# SCH_Mach_giao_tiep.net
KiCad netlist of a schematic drawn in Altium Designer
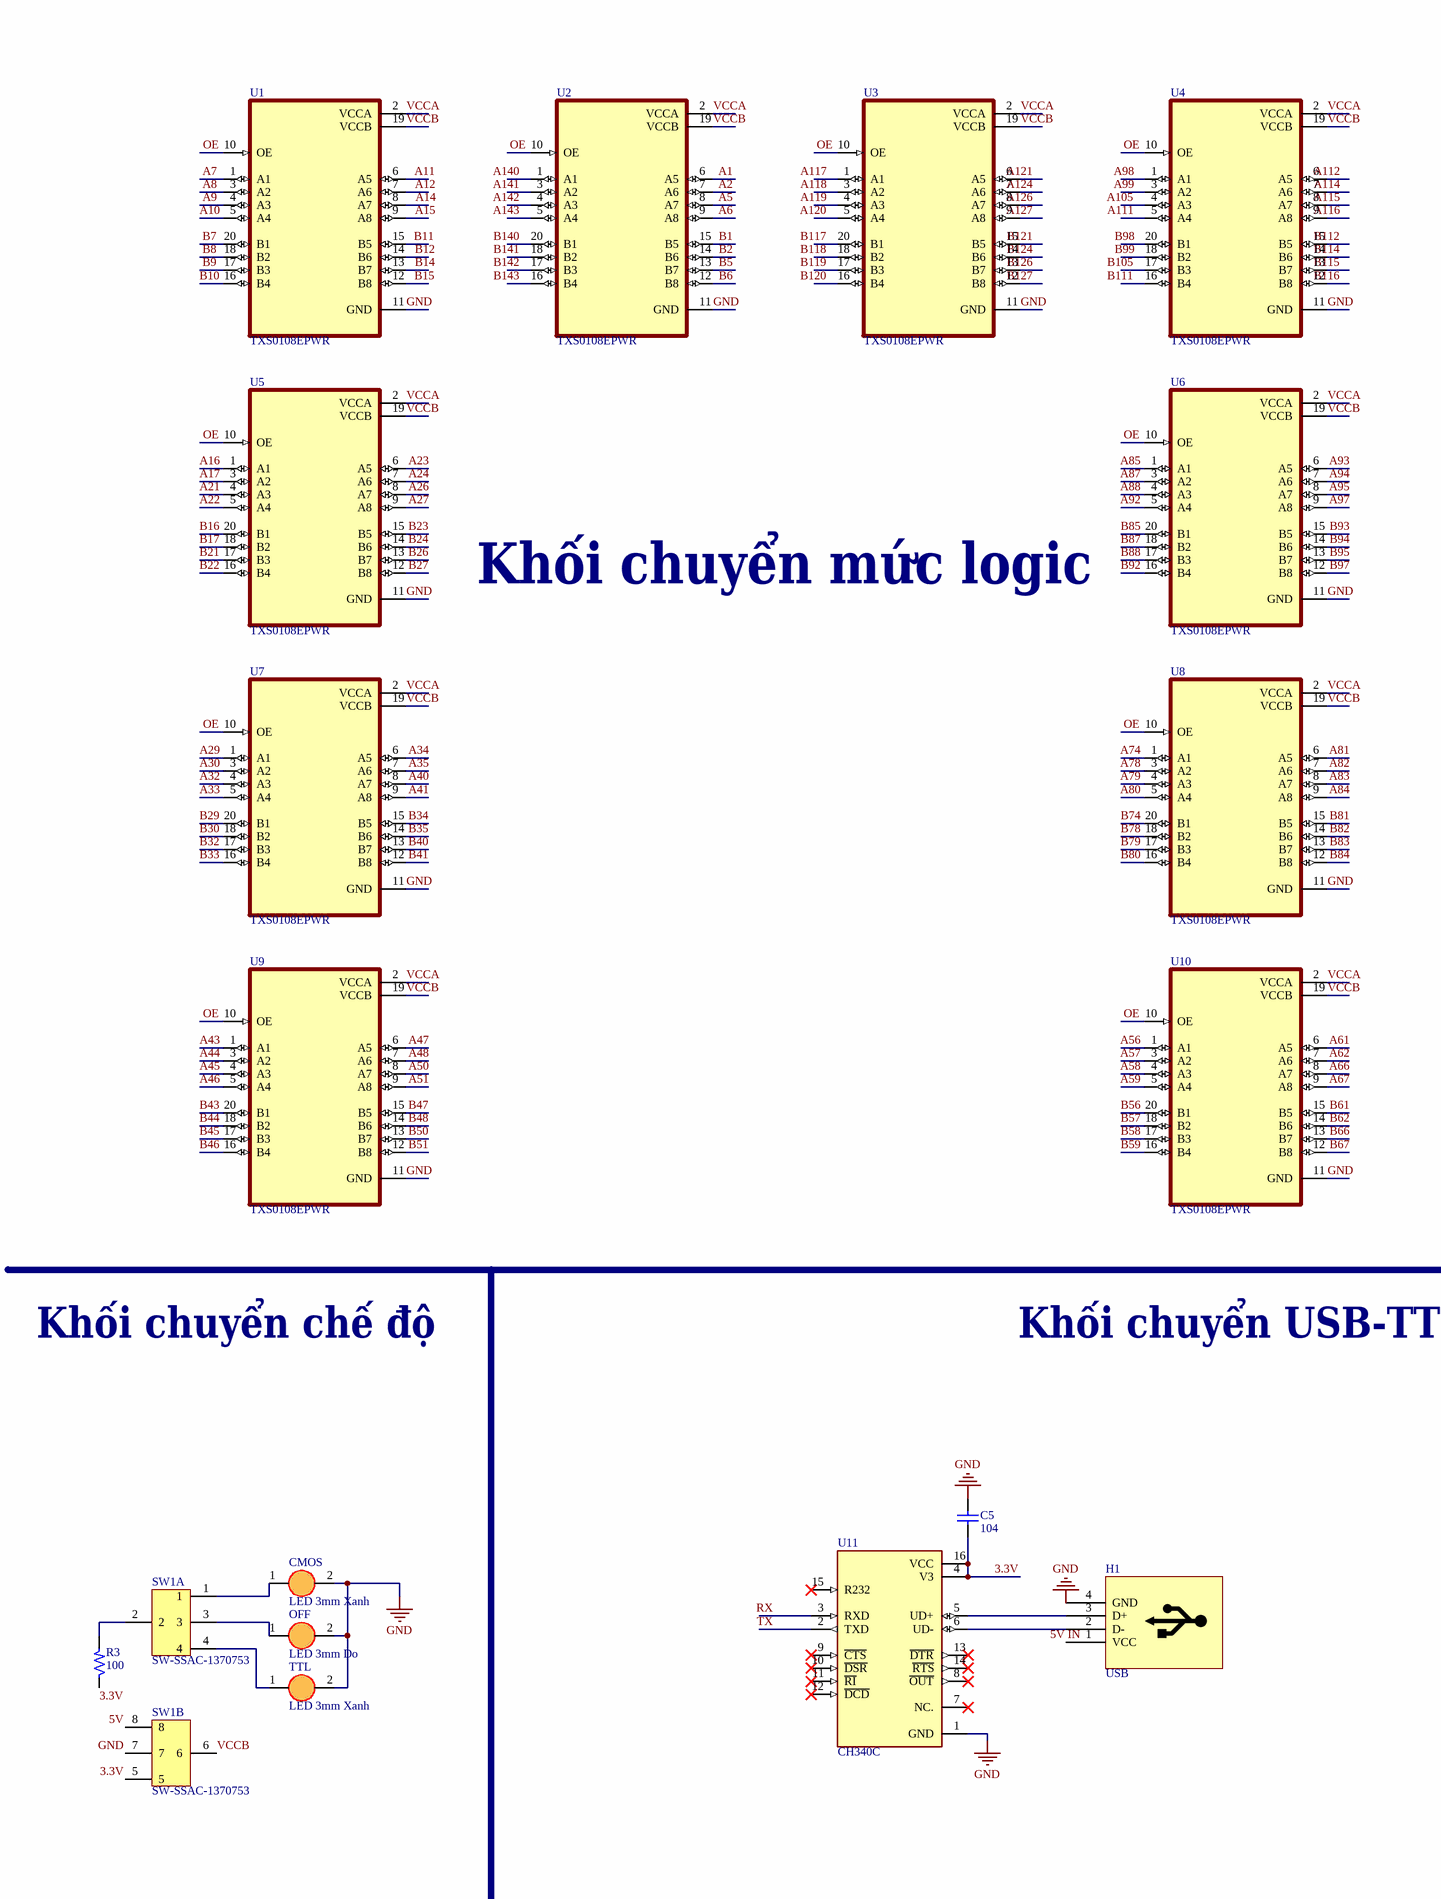
[diagram p0: SCH_Mach_giao_tiep.SchDoc, left]
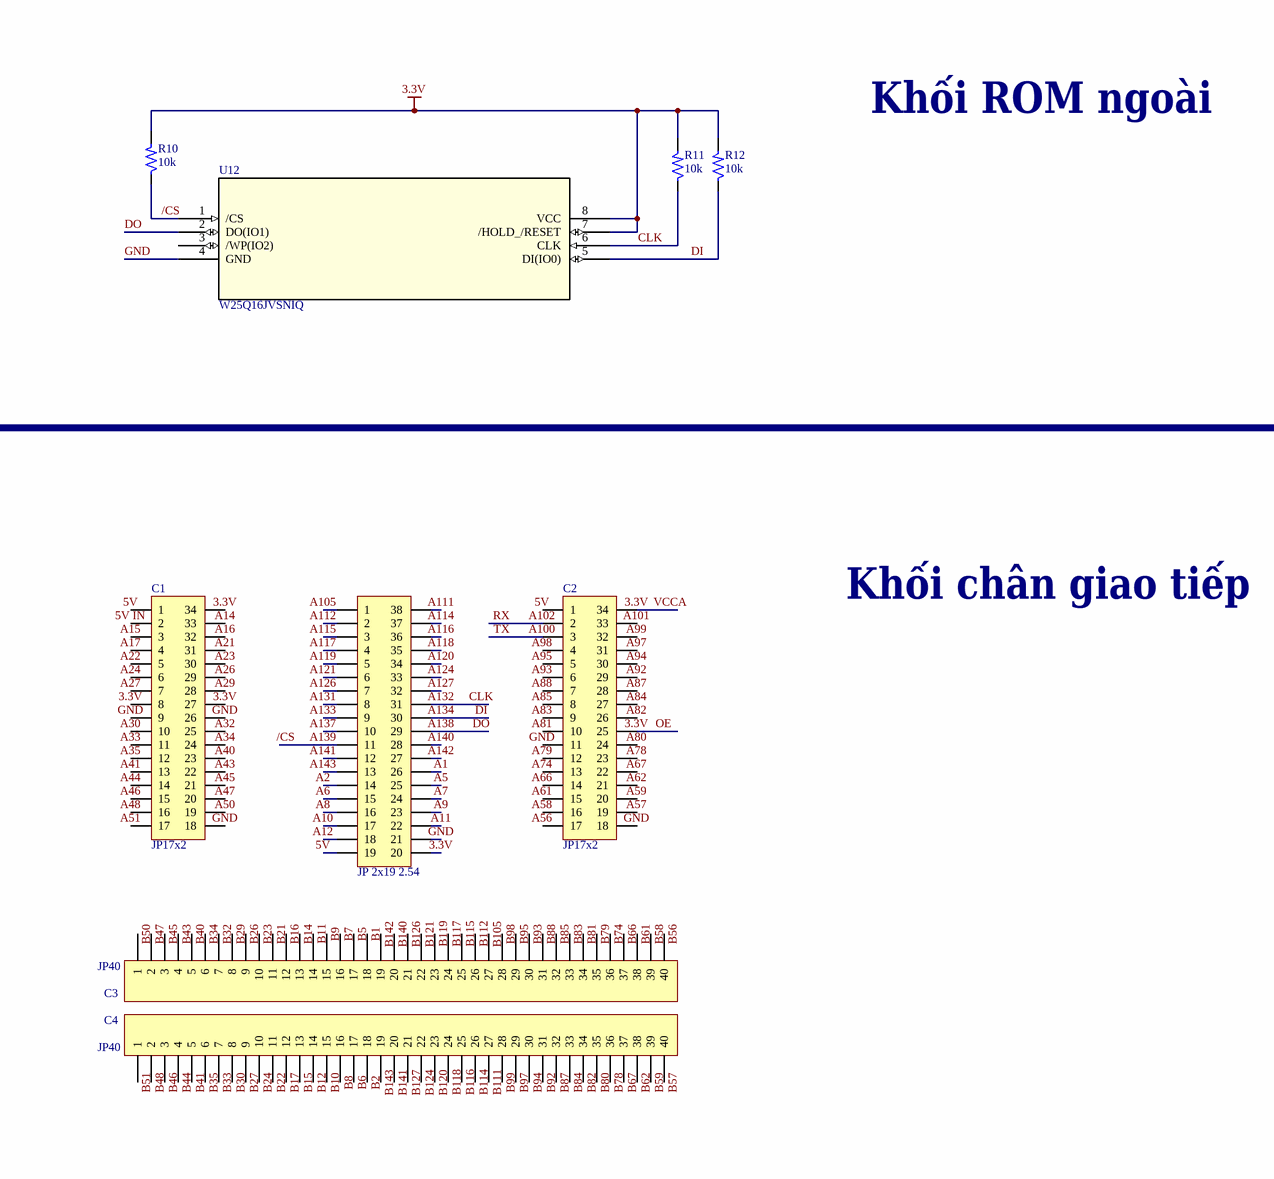
[diagram p1: SCH_Mach_giao_tiep.SchDoc, right]

(export (version "E")
  (design (tool "Eeschema 10.0.6"))
  (components
    (comp (ref "C1")
      (value "JP17x2")
      (footprint "JP17-C2T")
      (description "WR-PHD 2.54 mm Dual Socket Header")
      (fields
        (field (name "MANUFACTURER") "Würth Elektronik eiSos GmbH")
        (field (name "PARTNO") "61303421821")
        (field (name "CREATED BY") "Karrer Zheng")
      )
      (libsource (lib "LIBRARY") (part "JP17x2"))
    )
    (comp (ref "C2")
      (value "JP17x2")
      (footprint "JP17-C2T")
      (description "WR-PHD 2.54 mm Dual Socket Header")
      (fields
        (field (name "MANUFACTURER") "Würth Elektronik eiSos GmbH")
        (field (name "PARTNO") "61303421821")
        (field (name "CREATED BY") "Karrer Zheng")
      )
      (libsource (lib "LIBRARY") (part "JP17x2"))
    )
    (comp (ref "C3")
      (value "JP40")
      (footprint "JP40-D1T")
      (description "WR-PHD 2.54 mm Angled Socket Header")
      (fields
        (field (name "MANUFACTURER") "Würth Elektronik eiSos GmbH")
        (field (name "PARTNO") "613040143121")
        (field (name "CREATED BY") "Karrer Zheng")
      )
      (libsource (lib "") (part "JP40_1"))
    )
    (comp (ref "C4")
      (value "JP40")
      (footprint "JP40-D1T")
      (description "WR-PHD 2.54 mm Angled Socket Header")
      (fields
        (field (name "MANUFACTURER") "Würth Elektronik eiSos GmbH")
        (field (name "PARTNO") "613040143121")
        (field (name "CREATED BY") "Karrer Zheng")
      )
      (libsource (lib "LIBRARY") (part "JP40"))
    )
    (comp (ref "C5")
      (value "104")
      (footprint "tu gom")
      (description "Cắm")
      (libsource (lib "THU VIEN SCH") (part "Tu gom 104 50V"))
    )
    (comp (ref "CMOS")
      (value "LED 3mm Xanh")
      (footprint "LED 3MM XANH")
      (description "Cắm")
      (libsource (lib "THU VIEN SCH") (part "LED 3mm Xanh"))
    )
    (comp (ref "H1")
      (value "USB")
      (footprint "USB-B-STRANGE")
      (description "USB conector")
      (libsource (lib "Cty1") (part "USB"))
    )
    (comp (ref "JP1")
      (value "JP 2x19 2.54")
      (footprint "JP 2x20 CT")
      (description "Cắm")
      (libsource (lib "ThuVien") (part "JP 2x19 2.54 Cai Thang"))
    )
    (comp (ref "OFF")
      (value "LED 3mm Do")
      (footprint "LED 3mm Do")
      (description "Cắm")
      (libsource (lib "THU VIEN SCH") (part "LED 3mm Do"))
    )
    (comp (ref "R3")
      (value "100")
      (footprint "DIEN TRO 1/4 W")
      (description "Resistor 1/4W")
      (libsource (lib "Cty1") (part "Res"))
    )
    (comp (ref "R10")
      (value "10k")
      (footprint "SM-0805")
      (description "Resistor 1/4W")
      (libsource (lib "Cty1") (part "Res"))
    )
    (comp (ref "R11")
      (value "10k")
      (footprint "SM-0805")
      (description "Resistor 1/4W")
      (libsource (lib "Cty1") (part "Res"))
    )
    (comp (ref "R12")
      (value "10k")
      (footprint "SM-0805")
      (description "Resistor 1/4W")
      (libsource (lib "Cty1") (part "Res"))
    )
    (comp (ref "SW1")
      (value "SW-SSAC-1370753")
      (footprint "SW-SSAC-1370753")
      (libsource (lib "ThuVien") (part "SW-SSAC-1370753"))
    )
    (comp (ref "TTL")
      (value "LED 3mm Xanh")
      (footprint "LED 3MM XANH")
      (description "Cắm")
      (libsource (lib "THU VIEN SCH") (part "LED 3mm Xanh"))
    )
    (comp (ref "U1")
      (value "TXS0108EPWR")
      (footprint "SOP65P640X120-20N")
      (libsource (lib "ThuVien") (part "TXS0108EPWR"))
    )
    (comp (ref "U2")
      (value "TXS0108EPWR")
      (footprint "SOP65P640X120-20N")
      (libsource (lib "ThuVien") (part "TXS0108EPWR"))
    )
    (comp (ref "U3")
      (value "TXS0108EPWR")
      (footprint "SOP65P640X120-20N")
      (libsource (lib "ThuVien") (part "TXS0108EPWR"))
    )
    (comp (ref "U4")
      (value "TXS0108EPWR")
      (footprint "SOP65P640X120-20N")
      (libsource (lib "ThuVien") (part "TXS0108EPWR"))
    )
    (comp (ref "U5")
      (value "TXS0108EPWR")
      (footprint "SOP65P640X120-20N")
      (libsource (lib "ThuVien") (part "TXS0108EPWR"))
    )
    (comp (ref "U6")
      (value "TXS0108EPWR")
      (footprint "SOP65P640X120-20N")
      (libsource (lib "ThuVien") (part "TXS0108EPWR"))
    )
    (comp (ref "U7")
      (value "TXS0108EPWR")
      (footprint "SOP65P640X120-20N")
      (libsource (lib "ThuVien") (part "TXS0108EPWR"))
    )
    (comp (ref "U8")
      (value "TXS0108EPWR")
      (footprint "SOP65P640X120-20N")
      (libsource (lib "ThuVien") (part "TXS0108EPWR"))
    )
    (comp (ref "U9")
      (value "TXS0108EPWR")
      (footprint "SOP65P640X120-20N")
      (libsource (lib "ThuVien") (part "TXS0108EPWR"))
    )
    (comp (ref "U10")
      (value "TXS0108EPWR")
      (footprint "SOP65P640X120-20N")
      (libsource (lib "ThuVien") (part "TXS0108EPWR"))
    )
    (comp (ref "U11")
      (value "CH340C")
      (footprint "CH340C:SOIC127P600X180-16N")
      (description "USB to serial chip CH340")
      (fields (field (name "MF") "{'manufacturer': u'WCH'}"))
      (libsource (lib "ThuVien") (part "CH340C"))
    )
    (comp (ref "U12")
      (value "W25Q16JVSNIQ")
      (footprint "WIN_SS-8_WIN-M")
      (description "No Description Available")
      (fields (field (name "COPYRIGHT") "Copyright (C) 2022 Ultra Librarian. All rights reserved."))
      (libsource (lib "ThuVien") (part "W25Q16JVSNIQ"))
    )
  )
  (nets
    (net (code "1") (name "/5V") (class "Default")
      (node (ref "C1") (pin "1") (pinfunction "1_1") (pintype "passive"))
      (node (ref "C2") (pin "1") (pinfunction "1_1") (pintype "passive"))
      (node (ref "JP1") (pin "19") (pinfunction "19_19") (pintype "passive"))
      (node (ref "SW1") (pin "8") (pinfunction "8_8") (pintype "passive"))
    )
    (net (code "2") (name "/5V IN") (class "Default")
      (node (ref "C1") (pin "2") (pinfunction "2_2") (pintype "passive"))
      (node (ref "H1") (pin "1") (pinfunction "VCC_1") (pintype "passive"))
    )
    (net (code "3") (name "/A1") (class "Default")
      (node (ref "JP1") (pin "26") (pinfunction "26_26") (pintype "passive"))
      (node (ref "U2") (pin "6") (pinfunction "A5_6") (pintype "bidirectional"))
    )
    (net (code "4") (name "/A2") (class "Default")
      (node (ref "JP1") (pin "14") (pinfunction "14_14") (pintype "passive"))
      (node (ref "U2") (pin "7") (pinfunction "A6_7") (pintype "bidirectional"))
    )
    (net (code "5") (name "/A5") (class "Default")
      (node (ref "JP1") (pin "25") (pinfunction "25_25") (pintype "passive"))
      (node (ref "U2") (pin "8") (pinfunction "A7_8") (pintype "bidirectional"))
    )
    (net (code "6") (name "/A6") (class "Default")
      (node (ref "JP1") (pin "15") (pinfunction "15_15") (pintype "passive"))
      (node (ref "U2") (pin "9") (pinfunction "A8_9") (pintype "bidirectional"))
    )
    (net (code "7") (name "/A7") (class "Default")
      (node (ref "JP1") (pin "24") (pinfunction "24_24") (pintype "passive"))
      (node (ref "U1") (pin "1") (pinfunction "A1_1") (pintype "bidirectional"))
    )
    (net (code "8") (name "/A8") (class "Default")
      (node (ref "JP1") (pin "16") (pinfunction "16_16") (pintype "passive"))
      (node (ref "U1") (pin "3") (pinfunction "A2_3") (pintype "bidirectional"))
    )
    (net (code "9") (name "/A9") (class "Default")
      (node (ref "JP1") (pin "23") (pinfunction "23_23") (pintype "passive"))
      (node (ref "U1") (pin "4") (pinfunction "A3_4") (pintype "bidirectional"))
    )
    (net (code "10") (name "/A10") (class "Default")
      (node (ref "JP1") (pin "17") (pinfunction "17_17") (pintype "passive"))
      (node (ref "U1") (pin "5") (pinfunction "A4_5") (pintype "bidirectional"))
    )
    (net (code "11") (name "/A11") (class "Default")
      (node (ref "JP1") (pin "22") (pinfunction "22_22") (pintype "passive"))
      (node (ref "U1") (pin "6") (pinfunction "A5_6") (pintype "bidirectional"))
    )
    (net (code "12") (name "/A12") (class "Default")
      (node (ref "JP1") (pin "18") (pinfunction "18_18") (pintype "passive"))
      (node (ref "U1") (pin "7") (pinfunction "A6_7") (pintype "bidirectional"))
    )
    (net (code "13") (name "/A14") (class "Default")
      (node (ref "C1") (pin "33") (pinfunction "33_33") (pintype "passive"))
      (node (ref "U1") (pin "8") (pinfunction "A7_8") (pintype "bidirectional"))
    )
    (net (code "14") (name "/A15") (class "Default")
      (node (ref "C1") (pin "3") (pinfunction "3_3") (pintype "passive"))
      (node (ref "U1") (pin "9") (pinfunction "A8_9") (pintype "bidirectional"))
    )
    (net (code "15") (name "/A16") (class "Default")
      (node (ref "C1") (pin "32") (pinfunction "32_32") (pintype "passive"))
      (node (ref "U5") (pin "1") (pinfunction "A1_1") (pintype "bidirectional"))
    )
    (net (code "16") (name "/A17") (class "Default")
      (node (ref "C1") (pin "4") (pinfunction "4_4") (pintype "passive"))
      (node (ref "U5") (pin "3") (pinfunction "A2_3") (pintype "bidirectional"))
    )
    (net (code "17") (name "/A21") (class "Default")
      (node (ref "C1") (pin "31") (pinfunction "31_31") (pintype "passive"))
      (node (ref "U5") (pin "4") (pinfunction "A3_4") (pintype "bidirectional"))
    )
    (net (code "18") (name "/A22") (class "Default")
      (node (ref "C1") (pin "5") (pinfunction "5_5") (pintype "passive"))
      (node (ref "U5") (pin "5") (pinfunction "A4_5") (pintype "bidirectional"))
    )
    (net (code "19") (name "/A23") (class "Default")
      (node (ref "C1") (pin "30") (pinfunction "30_30") (pintype "passive"))
      (node (ref "U5") (pin "6") (pinfunction "A5_6") (pintype "bidirectional"))
    )
    (net (code "20") (name "/A24") (class "Default")
      (node (ref "C1") (pin "6") (pinfunction "6_6") (pintype "passive"))
      (node (ref "U5") (pin "7") (pinfunction "A6_7") (pintype "bidirectional"))
    )
    (net (code "21") (name "/A26") (class "Default")
      (node (ref "C1") (pin "29") (pinfunction "29_29") (pintype "passive"))
      (node (ref "U5") (pin "8") (pinfunction "A7_8") (pintype "bidirectional"))
    )
    (net (code "22") (name "/A27") (class "Default")
      (node (ref "C1") (pin "7") (pinfunction "7_7") (pintype "passive"))
      (node (ref "U5") (pin "9") (pinfunction "A8_9") (pintype "bidirectional"))
    )
    (net (code "23") (name "/A29") (class "Default")
      (node (ref "C1") (pin "28") (pinfunction "28_28") (pintype "passive"))
      (node (ref "U7") (pin "1") (pinfunction "A1_1") (pintype "bidirectional"))
    )
    (net (code "24") (name "/A30") (class "Default")
      (node (ref "C1") (pin "10") (pinfunction "10_10") (pintype "passive"))
      (node (ref "U7") (pin "3") (pinfunction "A2_3") (pintype "bidirectional"))
    )
    (net (code "25") (name "/A32") (class "Default")
      (node (ref "C1") (pin "25") (pinfunction "25_25") (pintype "passive"))
      (node (ref "U7") (pin "4") (pinfunction "A3_4") (pintype "bidirectional"))
    )
    (net (code "26") (name "/A33") (class "Default")
      (node (ref "C1") (pin "11") (pinfunction "11_11") (pintype "passive"))
      (node (ref "U7") (pin "5") (pinfunction "A4_5") (pintype "bidirectional"))
    )
    (net (code "27") (name "/A34") (class "Default")
      (node (ref "C1") (pin "24") (pinfunction "24_24") (pintype "passive"))
      (node (ref "U7") (pin "6") (pinfunction "A5_6") (pintype "bidirectional"))
    )
    (net (code "28") (name "/A35") (class "Default")
      (node (ref "C1") (pin "12") (pinfunction "12_12") (pintype "passive"))
      (node (ref "U7") (pin "7") (pinfunction "A6_7") (pintype "bidirectional"))
    )
    (net (code "29") (name "/A40") (class "Default")
      (node (ref "C1") (pin "23") (pinfunction "23_23") (pintype "passive"))
      (node (ref "U7") (pin "8") (pinfunction "A7_8") (pintype "bidirectional"))
    )
    (net (code "30") (name "/A41") (class "Default")
      (node (ref "C1") (pin "13") (pinfunction "13_13") (pintype "passive"))
      (node (ref "U7") (pin "9") (pinfunction "A8_9") (pintype "bidirectional"))
    )
    (net (code "31") (name "/A43") (class "Default")
      (node (ref "C1") (pin "22") (pinfunction "22_22") (pintype "passive"))
      (node (ref "U9") (pin "1") (pinfunction "A1_1") (pintype "bidirectional"))
    )
    (net (code "32") (name "/A44") (class "Default")
      (node (ref "C1") (pin "14") (pinfunction "14_14") (pintype "passive"))
      (node (ref "U9") (pin "3") (pinfunction "A2_3") (pintype "bidirectional"))
    )
    (net (code "33") (name "/A45") (class "Default")
      (node (ref "C1") (pin "21") (pinfunction "21_21") (pintype "passive"))
      (node (ref "U9") (pin "4") (pinfunction "A3_4") (pintype "bidirectional"))
    )
    (net (code "34") (name "/A46") (class "Default")
      (node (ref "C1") (pin "15") (pinfunction "15_15") (pintype "passive"))
      (node (ref "U9") (pin "5") (pinfunction "A4_5") (pintype "bidirectional"))
    )
    (net (code "35") (name "/A47") (class "Default")
      (node (ref "C1") (pin "20") (pinfunction "20_20") (pintype "passive"))
      (node (ref "U9") (pin "6") (pinfunction "A5_6") (pintype "bidirectional"))
    )
    (net (code "36") (name "/A48") (class "Default")
      (node (ref "C1") (pin "16") (pinfunction "16_16") (pintype "passive"))
      (node (ref "U9") (pin "7") (pinfunction "A6_7") (pintype "bidirectional"))
    )
    (net (code "37") (name "/A50") (class "Default")
      (node (ref "C1") (pin "19") (pinfunction "19_19") (pintype "passive"))
      (node (ref "U9") (pin "8") (pinfunction "A7_8") (pintype "bidirectional"))
    )
    (net (code "38") (name "/A51") (class "Default")
      (node (ref "C1") (pin "17") (pinfunction "17_17") (pintype "passive"))
      (node (ref "U9") (pin "9") (pinfunction "A8_9") (pintype "bidirectional"))
    )
    (net (code "39") (name "/A56") (class "Default")
      (node (ref "C2") (pin "17") (pinfunction "17_17") (pintype "passive"))
      (node (ref "U10") (pin "1") (pinfunction "A1_1") (pintype "bidirectional"))
    )
    (net (code "40") (name "/A57") (class "Default")
      (node (ref "C2") (pin "19") (pinfunction "19_19") (pintype "passive"))
      (node (ref "U10") (pin "3") (pinfunction "A2_3") (pintype "bidirectional"))
    )
    (net (code "41") (name "/A58") (class "Default")
      (node (ref "C2") (pin "16") (pinfunction "16_16") (pintype "passive"))
      (node (ref "U10") (pin "4") (pinfunction "A3_4") (pintype "bidirectional"))
    )
    (net (code "42") (name "/A59") (class "Default")
      (node (ref "C2") (pin "20") (pinfunction "20_20") (pintype "passive"))
      (node (ref "U10") (pin "5") (pinfunction "A4_5") (pintype "bidirectional"))
    )
    (net (code "43") (name "/A61") (class "Default")
      (node (ref "C2") (pin "15") (pinfunction "15_15") (pintype "passive"))
      (node (ref "U10") (pin "6") (pinfunction "A5_6") (pintype "bidirectional"))
    )
    (net (code "44") (name "/A62") (class "Default")
      (node (ref "C2") (pin "21") (pinfunction "21_21") (pintype "passive"))
      (node (ref "U10") (pin "7") (pinfunction "A6_7") (pintype "bidirectional"))
    )
    (net (code "45") (name "/A66") (class "Default")
      (node (ref "C2") (pin "14") (pinfunction "14_14") (pintype "passive"))
      (node (ref "U10") (pin "8") (pinfunction "A7_8") (pintype "bidirectional"))
    )
    (net (code "46") (name "/A67") (class "Default")
      (node (ref "C2") (pin "22") (pinfunction "22_22") (pintype "passive"))
      (node (ref "U10") (pin "9") (pinfunction "A8_9") (pintype "bidirectional"))
    )
    (net (code "47") (name "/A74") (class "Default")
      (node (ref "C2") (pin "13") (pinfunction "13_13") (pintype "passive"))
      (node (ref "U8") (pin "1") (pinfunction "A1_1") (pintype "bidirectional"))
    )
    (net (code "48") (name "/A78") (class "Default")
      (node (ref "C2") (pin "23") (pinfunction "23_23") (pintype "passive"))
      (node (ref "U8") (pin "3") (pinfunction "A2_3") (pintype "bidirectional"))
    )
    (net (code "49") (name "/A79") (class "Default")
      (node (ref "C2") (pin "12") (pinfunction "12_12") (pintype "passive"))
      (node (ref "U8") (pin "4") (pinfunction "A3_4") (pintype "bidirectional"))
    )
    (net (code "50") (name "/A80") (class "Default")
      (node (ref "C2") (pin "24") (pinfunction "24_24") (pintype "passive"))
      (node (ref "U8") (pin "5") (pinfunction "A4_5") (pintype "bidirectional"))
    )
    (net (code "51") (name "/A81") (class "Default")
      (node (ref "C2") (pin "10") (pinfunction "10_10") (pintype "passive"))
      (node (ref "U8") (pin "6") (pinfunction "A5_6") (pintype "bidirectional"))
    )
    (net (code "52") (name "/A82") (class "Default")
      (node (ref "C2") (pin "26") (pinfunction "26_26") (pintype "passive"))
      (node (ref "U8") (pin "7") (pinfunction "A6_7") (pintype "bidirectional"))
    )
    (net (code "53") (name "/A83") (class "Default")
      (node (ref "C2") (pin "9") (pinfunction "9_9") (pintype "passive"))
      (node (ref "U8") (pin "8") (pinfunction "A7_8") (pintype "bidirectional"))
    )
    (net (code "54") (name "/A84") (class "Default")
      (node (ref "C2") (pin "27") (pinfunction "27_27") (pintype "passive"))
      (node (ref "U8") (pin "9") (pinfunction "A8_9") (pintype "bidirectional"))
    )
    (net (code "55") (name "/A85") (class "Default")
      (node (ref "C2") (pin "8") (pinfunction "8_8") (pintype "passive"))
      (node (ref "U6") (pin "1") (pinfunction "A1_1") (pintype "bidirectional"))
    )
    (net (code "56") (name "/A87") (class "Default")
      (node (ref "C2") (pin "28") (pinfunction "28_28") (pintype "passive"))
      (node (ref "U6") (pin "3") (pinfunction "A2_3") (pintype "bidirectional"))
    )
    (net (code "57") (name "/A88") (class "Default")
      (node (ref "C2") (pin "7") (pinfunction "7_7") (pintype "passive"))
      (node (ref "U6") (pin "4") (pinfunction "A3_4") (pintype "bidirectional"))
    )
    (net (code "58") (name "/A92") (class "Default")
      (node (ref "C2") (pin "29") (pinfunction "29_29") (pintype "passive"))
      (node (ref "U6") (pin "5") (pinfunction "A4_5") (pintype "bidirectional"))
    )
    (net (code "59") (name "/A93") (class "Default")
      (node (ref "C2") (pin "6") (pinfunction "6_6") (pintype "passive"))
      (node (ref "U6") (pin "6") (pinfunction "A5_6") (pintype "bidirectional"))
    )
    (net (code "60") (name "/A94") (class "Default")
      (node (ref "C2") (pin "30") (pinfunction "30_30") (pintype "passive"))
      (node (ref "U6") (pin "7") (pinfunction "A6_7") (pintype "bidirectional"))
    )
    (net (code "61") (name "/A95") (class "Default")
      (node (ref "C2") (pin "5") (pinfunction "5_5") (pintype "passive"))
      (node (ref "U6") (pin "8") (pinfunction "A7_8") (pintype "bidirectional"))
    )
    (net (code "62") (name "/A97") (class "Default")
      (node (ref "C2") (pin "31") (pinfunction "31_31") (pintype "passive"))
      (node (ref "U6") (pin "9") (pinfunction "A8_9") (pintype "bidirectional"))
    )
    (net (code "63") (name "/A98") (class "Default")
      (node (ref "C2") (pin "4") (pinfunction "4_4") (pintype "passive"))
      (node (ref "U4") (pin "1") (pinfunction "A1_1") (pintype "bidirectional"))
    )
    (net (code "64") (name "/A99") (class "Default")
      (node (ref "C2") (pin "32") (pinfunction "32_32") (pintype "passive"))
      (node (ref "U4") (pin "3") (pinfunction "A2_3") (pintype "bidirectional"))
    )
    (net (code "65") (name "/A100") (class "Default")
      (node (ref "C2") (pin "3") (pinfunction "3_3") (pintype "passive"))
      (node (ref "U11") (pin "2") (pinfunction "TXD_2") (pintype "output"))
    )
    (net (code "66") (name "/A101") (class "Default")
      (node (ref "C2") (pin "33") (pinfunction "33_33") (pintype "passive"))
    )
    (net (code "67") (name "/A102") (class "Default")
      (node (ref "C2") (pin "2") (pinfunction "2_2") (pintype "passive"))
      (node (ref "U11") (pin "3") (pinfunction "RXD_3") (pintype "input"))
    )
    (net (code "68") (name "/A105") (class "Default")
      (node (ref "JP1") (pin "1") (pinfunction "1_1") (pintype "passive"))
      (node (ref "U4") (pin "4") (pinfunction "A3_4") (pintype "bidirectional"))
    )
    (net (code "69") (name "/A111") (class "Default")
      (node (ref "JP1") (pin "38") (pinfunction "38_38") (pintype "passive"))
      (node (ref "U4") (pin "5") (pinfunction "A4_5") (pintype "bidirectional"))
    )
    (net (code "70") (name "/A112") (class "Default")
      (node (ref "JP1") (pin "2") (pinfunction "2_2") (pintype "passive"))
      (node (ref "U4") (pin "6") (pinfunction "A5_6") (pintype "bidirectional"))
    )
    (net (code "71") (name "/A114") (class "Default")
      (node (ref "JP1") (pin "37") (pinfunction "37_37") (pintype "passive"))
      (node (ref "U4") (pin "7") (pinfunction "A6_7") (pintype "bidirectional"))
    )
    (net (code "72") (name "/A115") (class "Default")
      (node (ref "JP1") (pin "3") (pinfunction "3_3") (pintype "passive"))
      (node (ref "U4") (pin "8") (pinfunction "A7_8") (pintype "bidirectional"))
    )
    (net (code "73") (name "/A116") (class "Default")
      (node (ref "JP1") (pin "36") (pinfunction "36_36") (pintype "passive"))
      (node (ref "U4") (pin "9") (pinfunction "A8_9") (pintype "bidirectional"))
    )
    (net (code "74") (name "/A117") (class "Default")
      (node (ref "JP1") (pin "4") (pinfunction "4_4") (pintype "passive"))
      (node (ref "U3") (pin "1") (pinfunction "A1_1") (pintype "bidirectional"))
    )
    (net (code "75") (name "/A118") (class "Default")
      (node (ref "JP1") (pin "35") (pinfunction "35_35") (pintype "passive"))
      (node (ref "U3") (pin "3") (pinfunction "A2_3") (pintype "bidirectional"))
    )
    (net (code "76") (name "/A119") (class "Default")
      (node (ref "JP1") (pin "5") (pinfunction "5_5") (pintype "passive"))
      (node (ref "U3") (pin "4") (pinfunction "A3_4") (pintype "bidirectional"))
    )
    (net (code "77") (name "/A120") (class "Default")
      (node (ref "JP1") (pin "34") (pinfunction "34_34") (pintype "passive"))
      (node (ref "U3") (pin "5") (pinfunction "A4_5") (pintype "bidirectional"))
    )
    (net (code "78") (name "/A121") (class "Default")
      (node (ref "JP1") (pin "6") (pinfunction "6_6") (pintype "passive"))
      (node (ref "U3") (pin "6") (pinfunction "A5_6") (pintype "bidirectional"))
    )
    (net (code "79") (name "/A124") (class "Default")
      (node (ref "JP1") (pin "33") (pinfunction "33_33") (pintype "passive"))
      (node (ref "U3") (pin "7") (pinfunction "A6_7") (pintype "bidirectional"))
    )
    (net (code "80") (name "/A126") (class "Default")
      (node (ref "JP1") (pin "7") (pinfunction "7_7") (pintype "passive"))
      (node (ref "U3") (pin "8") (pinfunction "A7_8") (pintype "bidirectional"))
    )
    (net (code "81") (name "/A127") (class "Default")
      (node (ref "JP1") (pin "32") (pinfunction "32_32") (pintype "passive"))
      (node (ref "U3") (pin "9") (pinfunction "A8_9") (pintype "bidirectional"))
    )
    (net (code "82") (name "/A131") (class "Default")
      (node (ref "JP1") (pin "8") (pinfunction "8_8") (pintype "passive"))
    )
    (net (code "83") (name "/A132") (class "Default")
      (node (ref "JP1") (pin "31") (pinfunction "31_31") (pintype "passive"))
      (node (ref "R11") (pin "1") (pinfunction "1_1") (pintype "passive"))
      (node (ref "U12") (pin "6") (pinfunction "CLK_6") (pintype "input"))
    )
    (net (code "84") (name "/A133") (class "Default")
      (node (ref "JP1") (pin "9") (pinfunction "9_9") (pintype "passive"))
    )
    (net (code "85") (name "/A134") (class "Default")
      (node (ref "JP1") (pin "30") (pinfunction "30_30") (pintype "passive"))
      (node (ref "R12") (pin "1") (pinfunction "1_1") (pintype "passive"))
      (node (ref "U12") (pin "5") (pinfunction "DI(IO0)_5") (pintype "bidirectional"))
    )
    (net (code "86") (name "/A137") (class "Default")
      (node (ref "JP1") (pin "10") (pinfunction "10_10") (pintype "passive"))
    )
    (net (code "87") (name "/A138") (class "Default")
      (node (ref "JP1") (pin "29") (pinfunction "29_29") (pintype "passive"))
      (node (ref "U12") (pin "2") (pinfunction "DO(IO1)_2") (pintype "bidirectional"))
    )
    (net (code "88") (name "/A139") (class "Default")
      (node (ref "JP1") (pin "11") (pinfunction "11_11") (pintype "passive"))
      (node (ref "R10") (pin "1") (pinfunction "1_1") (pintype "passive"))
      (node (ref "U12") (pin "1") (pinfunction "/CS_1") (pintype "input"))
    )
    (net (code "89") (name "/A140") (class "Default")
      (node (ref "JP1") (pin "28") (pinfunction "28_28") (pintype "passive"))
      (node (ref "U2") (pin "1") (pinfunction "A1_1") (pintype "bidirectional"))
    )
    (net (code "90") (name "/A141") (class "Default")
      (node (ref "JP1") (pin "12") (pinfunction "12_12") (pintype "passive"))
      (node (ref "U2") (pin "3") (pinfunction "A2_3") (pintype "bidirectional"))
    )
    (net (code "91") (name "/A142") (class "Default")
      (node (ref "JP1") (pin "27") (pinfunction "27_27") (pintype "passive"))
      (node (ref "U2") (pin "4") (pinfunction "A3_4") (pintype "bidirectional"))
    )
    (net (code "92") (name "/A143") (class "Default")
      (node (ref "JP1") (pin "13") (pinfunction "13_13") (pintype "passive"))
      (node (ref "U2") (pin "5") (pinfunction "A4_5") (pintype "bidirectional"))
    )
    (net (code "93") (name "/B1") (class "Default")
      (node (ref "C3") (pin "18") (pinfunction "18_18") (pintype "passive"))
      (node (ref "U2") (pin "15") (pinfunction "B5_15") (pintype "bidirectional"))
    )
    (net (code "94") (name "/B2") (class "Default")
      (node (ref "C4") (pin "18") (pinfunction "18_18") (pintype "passive"))
      (node (ref "U2") (pin "14") (pinfunction "B6_14") (pintype "bidirectional"))
    )
    (net (code "95") (name "/B5") (class "Default")
      (node (ref "C3") (pin "17") (pinfunction "17_17") (pintype "passive"))
      (node (ref "U2") (pin "13") (pinfunction "B7_13") (pintype "bidirectional"))
    )
    (net (code "96") (name "/B6") (class "Default")
      (node (ref "C4") (pin "17") (pinfunction "17_17") (pintype "passive"))
      (node (ref "U2") (pin "12") (pinfunction "B8_12") (pintype "bidirectional"))
    )
    (net (code "97") (name "/B7") (class "Default")
      (node (ref "C3") (pin "16") (pinfunction "16_16") (pintype "passive"))
      (node (ref "U1") (pin "20") (pinfunction "B1_20") (pintype "bidirectional"))
    )
    (net (code "98") (name "/B8") (class "Default")
      (node (ref "C4") (pin "16") (pinfunction "16_16") (pintype "passive"))
      (node (ref "U1") (pin "18") (pinfunction "B2_18") (pintype "bidirectional"))
    )
    (net (code "99") (name "/B9") (class "Default")
      (node (ref "C3") (pin "15") (pinfunction "15_15") (pintype "passive"))
      (node (ref "U1") (pin "17") (pinfunction "B3_17") (pintype "bidirectional"))
    )
    (net (code "100") (name "/B10") (class "Default")
      (node (ref "C4") (pin "15") (pinfunction "15_15") (pintype "passive"))
      (node (ref "U1") (pin "16") (pinfunction "B4_16") (pintype "bidirectional"))
    )
    (net (code "101") (name "/B11") (class "Default")
      (node (ref "C3") (pin "14") (pinfunction "14_14") (pintype "passive"))
      (node (ref "U1") (pin "15") (pinfunction "B5_15") (pintype "bidirectional"))
    )
    (net (code "102") (name "/B12") (class "Default")
      (node (ref "C4") (pin "14") (pinfunction "14_14") (pintype "passive"))
      (node (ref "U1") (pin "14") (pinfunction "B6_14") (pintype "bidirectional"))
    )
    (net (code "103") (name "/B14") (class "Default")
      (node (ref "C3") (pin "13") (pinfunction "13_13") (pintype "passive"))
      (node (ref "U1") (pin "13") (pinfunction "B7_13") (pintype "bidirectional"))
    )
    (net (code "104") (name "/B15") (class "Default")
      (node (ref "C4") (pin "13") (pinfunction "13_13") (pintype "passive"))
      (node (ref "U1") (pin "12") (pinfunction "B8_12") (pintype "bidirectional"))
    )
    (net (code "105") (name "/B16") (class "Default")
      (node (ref "C3") (pin "12") (pinfunction "12_12") (pintype "passive"))
      (node (ref "U5") (pin "20") (pinfunction "B1_20") (pintype "bidirectional"))
    )
    (net (code "106") (name "/B17") (class "Default")
      (node (ref "C4") (pin "12") (pinfunction "12_12") (pintype "passive"))
      (node (ref "U5") (pin "18") (pinfunction "B2_18") (pintype "bidirectional"))
    )
    (net (code "107") (name "/B21") (class "Default")
      (node (ref "C3") (pin "11") (pinfunction "11_11") (pintype "passive"))
      (node (ref "U5") (pin "17") (pinfunction "B3_17") (pintype "bidirectional"))
    )
    (net (code "108") (name "/B22") (class "Default")
      (node (ref "C4") (pin "11") (pinfunction "11_11") (pintype "passive"))
      (node (ref "U5") (pin "16") (pinfunction "B4_16") (pintype "bidirectional"))
    )
    (net (code "109") (name "/B23") (class "Default")
      (node (ref "C3") (pin "10") (pinfunction "10_10") (pintype "passive"))
      (node (ref "U5") (pin "15") (pinfunction "B5_15") (pintype "bidirectional"))
    )
    (net (code "110") (name "/B24") (class "Default")
      (node (ref "C4") (pin "10") (pinfunction "10_10") (pintype "passive"))
      (node (ref "U5") (pin "14") (pinfunction "B6_14") (pintype "bidirectional"))
    )
    (net (code "111") (name "/B26") (class "Default")
      (node (ref "C3") (pin "9") (pinfunction "9_9") (pintype "passive"))
      (node (ref "U5") (pin "13") (pinfunction "B7_13") (pintype "bidirectional"))
    )
    (net (code "112") (name "/B27") (class "Default")
      (node (ref "C4") (pin "9") (pinfunction "9_9") (pintype "passive"))
      (node (ref "U5") (pin "12") (pinfunction "B8_12") (pintype "bidirectional"))
    )
    (net (code "113") (name "/B29") (class "Default")
      (node (ref "C3") (pin "8") (pinfunction "8_8") (pintype "passive"))
      (node (ref "U7") (pin "20") (pinfunction "B1_20") (pintype "bidirectional"))
    )
    (net (code "114") (name "/B30") (class "Default")
      (node (ref "C4") (pin "8") (pinfunction "8_8") (pintype "passive"))
      (node (ref "U7") (pin "18") (pinfunction "B2_18") (pintype "bidirectional"))
    )
    (net (code "115") (name "/B32") (class "Default")
      (node (ref "C3") (pin "7") (pinfunction "7_7") (pintype "passive"))
      (node (ref "U7") (pin "17") (pinfunction "B3_17") (pintype "bidirectional"))
    )
    (net (code "116") (name "/B33") (class "Default")
      (node (ref "C4") (pin "7") (pinfunction "7_7") (pintype "passive"))
      (node (ref "U7") (pin "16") (pinfunction "B4_16") (pintype "bidirectional"))
    )
    (net (code "117") (name "/B34") (class "Default")
      (node (ref "C3") (pin "6") (pinfunction "6_6") (pintype "passive"))
      (node (ref "U7") (pin "15") (pinfunction "B5_15") (pintype "bidirectional"))
    )
    (net (code "118") (name "/B35") (class "Default")
      (node (ref "C4") (pin "6") (pinfunction "6_6") (pintype "passive"))
      (node (ref "U7") (pin "14") (pinfunction "B6_14") (pintype "bidirectional"))
    )
    (net (code "119") (name "/B40") (class "Default")
      (node (ref "C3") (pin "5") (pinfunction "5_5") (pintype "passive"))
      (node (ref "U7") (pin "13") (pinfunction "B7_13") (pintype "bidirectional"))
    )
    (net (code "120") (name "/B41") (class "Default")
      (node (ref "C4") (pin "5") (pinfunction "5_5") (pintype "passive"))
      (node (ref "U7") (pin "12") (pinfunction "B8_12") (pintype "bidirectional"))
    )
    (net (code "121") (name "/B43") (class "Default")
      (node (ref "C3") (pin "4") (pinfunction "4_4") (pintype "passive"))
      (node (ref "U9") (pin "20") (pinfunction "B1_20") (pintype "bidirectional"))
    )
    (net (code "122") (name "/B44") (class "Default")
      (node (ref "C4") (pin "4") (pinfunction "4_4") (pintype "passive"))
      (node (ref "U9") (pin "18") (pinfunction "B2_18") (pintype "bidirectional"))
    )
    (net (code "123") (name "/B45") (class "Default")
      (node (ref "C3") (pin "3") (pinfunction "3_3") (pintype "passive"))
      (node (ref "U9") (pin "17") (pinfunction "B3_17") (pintype "bidirectional"))
    )
    (net (code "124") (name "/B46") (class "Default")
      (node (ref "C4") (pin "3") (pinfunction "3_3") (pintype "passive"))
      (node (ref "U9") (pin "16") (pinfunction "B4_16") (pintype "bidirectional"))
    )
    (net (code "125") (name "/B47") (class "Default")
      (node (ref "C3") (pin "2") (pinfunction "2_2") (pintype "passive"))
      (node (ref "U9") (pin "15") (pinfunction "B5_15") (pintype "bidirectional"))
    )
    (net (code "126") (name "/B48") (class "Default")
      (node (ref "C4") (pin "2") (pinfunction "2_2") (pintype "passive"))
      (node (ref "U9") (pin "14") (pinfunction "B6_14") (pintype "bidirectional"))
    )
    (net (code "127") (name "/B50") (class "Default")
      (node (ref "C3") (pin "1") (pinfunction "1_1") (pintype "passive"))
      (node (ref "U9") (pin "13") (pinfunction "B7_13") (pintype "bidirectional"))
    )
    (net (code "128") (name "/B51") (class "Default")
      (node (ref "C4") (pin "1") (pinfunction "1_1") (pintype "passive"))
      (node (ref "U9") (pin "12") (pinfunction "B8_12") (pintype "bidirectional"))
    )
    (net (code "129") (name "/B56") (class "Default")
      (node (ref "C3") (pin "40") (pinfunction "40_40") (pintype "passive"))
      (node (ref "U10") (pin "20") (pinfunction "B1_20") (pintype "bidirectional"))
    )
    (net (code "130") (name "/B57") (class "Default")
      (node (ref "C4") (pin "40") (pinfunction "40_40") (pintype "passive"))
      (node (ref "U10") (pin "18") (pinfunction "B2_18") (pintype "bidirectional"))
    )
    (net (code "131") (name "/B58") (class "Default")
      (node (ref "C3") (pin "39") (pinfunction "39_39") (pintype "passive"))
      (node (ref "U10") (pin "17") (pinfunction "B3_17") (pintype "bidirectional"))
    )
    (net (code "132") (name "/B59") (class "Default")
      (node (ref "C4") (pin "39") (pinfunction "39_39") (pintype "passive"))
      (node (ref "U10") (pin "16") (pinfunction "B4_16") (pintype "bidirectional"))
    )
    (net (code "133") (name "/B61") (class "Default")
      (node (ref "C3") (pin "38") (pinfunction "38_38") (pintype "passive"))
      (node (ref "U10") (pin "15") (pinfunction "B5_15") (pintype "bidirectional"))
    )
    (net (code "134") (name "/B62") (class "Default")
      (node (ref "C4") (pin "38") (pinfunction "38_38") (pintype "passive"))
      (node (ref "U10") (pin "14") (pinfunction "B6_14") (pintype "bidirectional"))
    )
    (net (code "135") (name "/B66") (class "Default")
      (node (ref "C3") (pin "37") (pinfunction "37_37") (pintype "passive"))
      (node (ref "U10") (pin "13") (pinfunction "B7_13") (pintype "bidirectional"))
    )
    (net (code "136") (name "/B67") (class "Default")
      (node (ref "C4") (pin "37") (pinfunction "37_37") (pintype "passive"))
      (node (ref "U10") (pin "12") (pinfunction "B8_12") (pintype "bidirectional"))
    )
    (net (code "137") (name "/B74") (class "Default")
      (node (ref "C3") (pin "36") (pinfunction "36_36") (pintype "passive"))
      (node (ref "U8") (pin "20") (pinfunction "B1_20") (pintype "bidirectional"))
    )
    (net (code "138") (name "/B78") (class "Default")
      (node (ref "C4") (pin "36") (pinfunction "36_36") (pintype "passive"))
      (node (ref "U8") (pin "18") (pinfunction "B2_18") (pintype "bidirectional"))
    )
    (net (code "139") (name "/B79") (class "Default")
      (node (ref "C3") (pin "35") (pinfunction "35_35") (pintype "passive"))
      (node (ref "U8") (pin "17") (pinfunction "B3_17") (pintype "bidirectional"))
    )
    (net (code "140") (name "/B80") (class "Default")
      (node (ref "C4") (pin "35") (pinfunction "35_35") (pintype "passive"))
      (node (ref "U8") (pin "16") (pinfunction "B4_16") (pintype "bidirectional"))
    )
    (net (code "141") (name "/B81") (class "Default")
      (node (ref "C3") (pin "34") (pinfunction "34_34") (pintype "passive"))
      (node (ref "U8") (pin "15") (pinfunction "B5_15") (pintype "bidirectional"))
    )
    (net (code "142") (name "/B82") (class "Default")
      (node (ref "C4") (pin "34") (pinfunction "34_34") (pintype "passive"))
      (node (ref "U8") (pin "14") (pinfunction "B6_14") (pintype "bidirectional"))
    )
    (net (code "143") (name "/B83") (class "Default")
      (node (ref "C3") (pin "33") (pinfunction "33_33") (pintype "passive"))
      (node (ref "U8") (pin "13") (pinfunction "B7_13") (pintype "bidirectional"))
    )
    (net (code "144") (name "/B84") (class "Default")
      (node (ref "C4") (pin "33") (pinfunction "33_33") (pintype "passive"))
      (node (ref "U8") (pin "12") (pinfunction "B8_12") (pintype "bidirectional"))
    )
    (net (code "145") (name "/B85") (class "Default")
      (node (ref "C3") (pin "32") (pinfunction "32_32") (pintype "passive"))
      (node (ref "U6") (pin "20") (pinfunction "B1_20") (pintype "bidirectional"))
    )
    (net (code "146") (name "/B87") (class "Default")
      (node (ref "C4") (pin "32") (pinfunction "32_32") (pintype "passive"))
      (node (ref "U6") (pin "18") (pinfunction "B2_18") (pintype "bidirectional"))
    )
    (net (code "147") (name "/B88") (class "Default")
      (node (ref "C3") (pin "31") (pinfunction "31_31") (pintype "passive"))
      (node (ref "U6") (pin "17") (pinfunction "B3_17") (pintype "bidirectional"))
    )
    (net (code "148") (name "/B92") (class "Default")
      (node (ref "C4") (pin "31") (pinfunction "31_31") (pintype "passive"))
      (node (ref "U6") (pin "16") (pinfunction "B4_16") (pintype "bidirectional"))
    )
    (net (code "149") (name "/B93") (class "Default")
      (node (ref "C3") (pin "30") (pinfunction "30_30") (pintype "passive"))
      (node (ref "U6") (pin "15") (pinfunction "B5_15") (pintype "bidirectional"))
    )
    (net (code "150") (name "/B94") (class "Default")
      (node (ref "C4") (pin "30") (pinfunction "30_30") (pintype "passive"))
      (node (ref "U6") (pin "14") (pinfunction "B6_14") (pintype "bidirectional"))
    )
    (net (code "151") (name "/B95") (class "Default")
      (node (ref "C3") (pin "29") (pinfunction "29_29") (pintype "passive"))
      (node (ref "U6") (pin "13") (pinfunction "B7_13") (pintype "bidirectional"))
    )
    (net (code "152") (name "/B97") (class "Default")
      (node (ref "C4") (pin "29") (pinfunction "29_29") (pintype "passive"))
      (node (ref "U6") (pin "12") (pinfunction "B8_12") (pintype "bidirectional"))
    )
    (net (code "153") (name "/B98") (class "Default")
      (node (ref "C3") (pin "28") (pinfunction "28_28") (pintype "passive"))
      (node (ref "U4") (pin "20") (pinfunction "B1_20") (pintype "bidirectional"))
    )
    (net (code "154") (name "/B99") (class "Default")
      (node (ref "C4") (pin "28") (pinfunction "28_28") (pintype "passive"))
      (node (ref "U4") (pin "18") (pinfunction "B2_18") (pintype "bidirectional"))
    )
    (net (code "155") (name "/B105") (class "Default")
      (node (ref "C3") (pin "27") (pinfunction "27_27") (pintype "passive"))
      (node (ref "U4") (pin "17") (pinfunction "B3_17") (pintype "bidirectional"))
    )
    (net (code "156") (name "/B111") (class "Default")
      (node (ref "C4") (pin "27") (pinfunction "27_27") (pintype "passive"))
      (node (ref "U4") (pin "16") (pinfunction "B4_16") (pintype "bidirectional"))
    )
    (net (code "157") (name "/B112") (class "Default")
      (node (ref "C3") (pin "26") (pinfunction "26_26") (pintype "passive"))
      (node (ref "U4") (pin "15") (pinfunction "B5_15") (pintype "bidirectional"))
    )
    (net (code "158") (name "/B114") (class "Default")
      (node (ref "C4") (pin "26") (pinfunction "26_26") (pintype "passive"))
      (node (ref "U4") (pin "14") (pinfunction "B6_14") (pintype "bidirectional"))
    )
    (net (code "159") (name "/B115") (class "Default")
      (node (ref "C3") (pin "25") (pinfunction "25_25") (pintype "passive"))
      (node (ref "U4") (pin "13") (pinfunction "B7_13") (pintype "bidirectional"))
    )
    (net (code "160") (name "/B116") (class "Default")
      (node (ref "C4") (pin "25") (pinfunction "25_25") (pintype "passive"))
      (node (ref "U4") (pin "12") (pinfunction "B8_12") (pintype "bidirectional"))
    )
    (net (code "161") (name "/B117") (class "Default")
      (node (ref "C3") (pin "24") (pinfunction "24_24") (pintype "passive"))
      (node (ref "U3") (pin "20") (pinfunction "B1_20") (pintype "bidirectional"))
    )
    (net (code "162") (name "/B118") (class "Default")
      (node (ref "C4") (pin "24") (pinfunction "24_24") (pintype "passive"))
      (node (ref "U3") (pin "18") (pinfunction "B2_18") (pintype "bidirectional"))
    )
    (net (code "163") (name "/B119") (class "Default")
      (node (ref "C3") (pin "23") (pinfunction "23_23") (pintype "passive"))
      (node (ref "U3") (pin "17") (pinfunction "B3_17") (pintype "bidirectional"))
    )
    (net (code "164") (name "/B120") (class "Default")
      (node (ref "C4") (pin "23") (pinfunction "23_23") (pintype "passive"))
      (node (ref "U3") (pin "16") (pinfunction "B4_16") (pintype "bidirectional"))
    )
    (net (code "165") (name "/B121") (class "Default")
      (node (ref "C3") (pin "22") (pinfunction "22_22") (pintype "passive"))
      (node (ref "U3") (pin "15") (pinfunction "B5_15") (pintype "bidirectional"))
    )
    (net (code "166") (name "/B124") (class "Default")
      (node (ref "C4") (pin "22") (pinfunction "22_22") (pintype "passive"))
      (node (ref "U3") (pin "14") (pinfunction "B6_14") (pintype "bidirectional"))
    )
    (net (code "167") (name "/B126") (class "Default")
      (node (ref "C3") (pin "21") (pinfunction "21_21") (pintype "passive"))
      (node (ref "U3") (pin "13") (pinfunction "B7_13") (pintype "bidirectional"))
    )
    (net (code "168") (name "/B127") (class "Default")
      (node (ref "C4") (pin "21") (pinfunction "21_21") (pintype "passive"))
      (node (ref "U3") (pin "12") (pinfunction "B8_12") (pintype "bidirectional"))
    )
    (net (code "169") (name "/B140") (class "Default")
      (node (ref "C3") (pin "20") (pinfunction "20_20") (pintype "passive"))
      (node (ref "U2") (pin "20") (pinfunction "B1_20") (pintype "bidirectional"))
    )
    (net (code "170") (name "/B141") (class "Default")
      (node (ref "C4") (pin "20") (pinfunction "20_20") (pintype "passive"))
      (node (ref "U2") (pin "18") (pinfunction "B2_18") (pintype "bidirectional"))
    )
    (net (code "171") (name "/B142") (class "Default")
      (node (ref "C3") (pin "19") (pinfunction "19_19") (pintype "passive"))
      (node (ref "U2") (pin "17") (pinfunction "B3_17") (pintype "bidirectional"))
    )
    (net (code "172") (name "/B143") (class "Default")
      (node (ref "C4") (pin "19") (pinfunction "19_19") (pintype "passive"))
      (node (ref "U2") (pin "16") (pinfunction "B4_16") (pintype "bidirectional"))
    )
    (net (code "173") (name "/VCCB") (class "Default")
      (node (ref "SW1") (pin "6") (pinfunction "6_6") (pintype "passive"))
      (node (ref "U1") (pin "19") (pinfunction "VCCB_19") (pintype "power_in"))
      (node (ref "U10") (pin "19") (pinfunction "VCCB_19") (pintype "power_in"))
      (node (ref "U2") (pin "19") (pinfunction "VCCB_19") (pintype "power_in"))
      (node (ref "U3") (pin "19") (pinfunction "VCCB_19") (pintype "power_in"))
      (node (ref "U4") (pin "19") (pinfunction "VCCB_19") (pintype "power_in"))
      (node (ref "U5") (pin "19") (pinfunction "VCCB_19") (pintype "power_in"))
      (node (ref "U6") (pin "19") (pinfunction "VCCB_19") (pintype "power_in"))
      (node (ref "U7") (pin "19") (pinfunction "VCCB_19") (pintype "power_in"))
      (node (ref "U8") (pin "19") (pinfunction "VCCB_19") (pintype "power_in"))
      (node (ref "U9") (pin "19") (pinfunction "VCCB_19") (pintype "power_in"))
    )
    (net (code "174") (name "3.3V") (class "Default")
      (node (ref "C1") (pin "27") (pinfunction "27_27") (pintype "passive"))
      (node (ref "C1") (pin "34") (pinfunction "34_34") (pintype "passive"))
      (node (ref "C1") (pin "8") (pinfunction "8_8") (pintype "passive"))
      (node (ref "C2") (pin "25") (pinfunction "25_25") (pintype "passive"))
      (node (ref "C2") (pin "34") (pinfunction "34_34") (pintype "passive"))
      (node (ref "C5") (pin "1") (pinfunction "1_1") (pintype "passive"))
      (node (ref "JP1") (pin "20") (pinfunction "20_20") (pintype "passive"))
      (node (ref "R10") (pin "2") (pinfunction "2_2") (pintype "passive"))
      (node (ref "R11") (pin "2") (pinfunction "2_2") (pintype "passive"))
      (node (ref "R12") (pin "2") (pinfunction "2_2") (pintype "passive"))
      (node (ref "R3") (pin "1") (pinfunction "1_1") (pintype "passive"))
      (node (ref "SW1") (pin "5") (pinfunction "5_5") (pintype "passive"))
      (node (ref "U1") (pin "10") (pinfunction "OE_10") (pintype "input"))
      (node (ref "U1") (pin "2") (pinfunction "VCCA_2") (pintype "power_in"))
      (node (ref "U10") (pin "10") (pinfunction "OE_10") (pintype "input"))
      (node (ref "U10") (pin "2") (pinfunction "VCCA_2") (pintype "power_in"))
      (node (ref "U11") (pin "16") (pinfunction "VCC_16") (pintype "power_in"))
      (node (ref "U11") (pin "4") (pinfunction "V3_4") (pintype "power_in"))
      (node (ref "U12") (pin "7") (pinfunction "/HOLD_/RESET_7") (pintype "bidirectional"))
      (node (ref "U12") (pin "8") (pinfunction "VCC_8") (pintype "power_in"))
      (node (ref "U2") (pin "10") (pinfunction "OE_10") (pintype "input"))
      (node (ref "U2") (pin "2") (pinfunction "VCCA_2") (pintype "power_in"))
      (node (ref "U3") (pin "10") (pinfunction "OE_10") (pintype "input"))
      (node (ref "U3") (pin "2") (pinfunction "VCCA_2") (pintype "power_in"))
      (node (ref "U4") (pin "10") (pinfunction "OE_10") (pintype "input"))
      (node (ref "U4") (pin "2") (pinfunction "VCCA_2") (pintype "power_in"))
      (node (ref "U5") (pin "10") (pinfunction "OE_10") (pintype "input"))
      (node (ref "U5") (pin "2") (pinfunction "VCCA_2") (pintype "power_in"))
      (node (ref "U6") (pin "10") (pinfunction "OE_10") (pintype "input"))
      (node (ref "U6") (pin "2") (pinfunction "VCCA_2") (pintype "power_in"))
      (node (ref "U7") (pin "10") (pinfunction "OE_10") (pintype "input"))
      (node (ref "U7") (pin "2") (pinfunction "VCCA_2") (pintype "power_in"))
      (node (ref "U8") (pin "10") (pinfunction "OE_10") (pintype "input"))
      (node (ref "U8") (pin "2") (pinfunction "VCCA_2") (pintype "power_in"))
      (node (ref "U9") (pin "10") (pinfunction "OE_10") (pintype "input"))
      (node (ref "U9") (pin "2") (pinfunction "VCCA_2") (pintype "power_in"))
    )
    (net (code "175") (name "GND") (class "Default")
      (node (ref "C1") (pin "18") (pinfunction "18_18") (pintype "passive"))
      (node (ref "C1") (pin "26") (pinfunction "26_26") (pintype "passive"))
      (node (ref "C1") (pin "9") (pinfunction "9_9") (pintype "passive"))
      (node (ref "C2") (pin "11") (pinfunction "11_11") (pintype "passive"))
      (node (ref "C2") (pin "18") (pinfunction "18_18") (pintype "passive"))
      (node (ref "C5") (pin "2") (pinfunction "2_2") (pintype "passive"))
      (node (ref "CMOS") (pin "2") (pinfunction "K_2") (pintype "passive"))
      (node (ref "H1") (pin "4") (pinfunction "GND_4") (pintype "passive"))
      (node (ref "JP1") (pin "21") (pinfunction "21_21") (pintype "passive"))
      (node (ref "OFF") (pin "2") (pinfunction "K_2") (pintype "passive"))
      (node (ref "SW1") (pin "7") (pinfunction "7_7") (pintype "passive"))
      (node (ref "TTL") (pin "2") (pinfunction "K_2") (pintype "passive"))
      (node (ref "U1") (pin "11") (pinfunction "GND_11") (pintype "power_in"))
      (node (ref "U10") (pin "11") (pinfunction "GND_11") (pintype "power_in"))
      (node (ref "U11") (pin "1") (pinfunction "GND_1") (pintype "power_in"))
      (node (ref "U12") (pin "4") (pinfunction "GND_4") (pintype "passive"))
      (node (ref "U2") (pin "11") (pinfunction "GND_11") (pintype "power_in"))
      (node (ref "U3") (pin "11") (pinfunction "GND_11") (pintype "power_in"))
      (node (ref "U4") (pin "11") (pinfunction "GND_11") (pintype "power_in"))
      (node (ref "U5") (pin "11") (pinfunction "GND_11") (pintype "power_in"))
      (node (ref "U6") (pin "11") (pinfunction "GND_11") (pintype "power_in"))
      (node (ref "U7") (pin "11") (pinfunction "GND_11") (pintype "power_in"))
      (node (ref "U8") (pin "11") (pinfunction "GND_11") (pintype "power_in"))
      (node (ref "U9") (pin "11") (pinfunction "GND_11") (pintype "power_in"))
    )
    (net (code "176") (name "Net-(CMOS-A)") (class "Default")
      (node (ref "CMOS") (pin "1") (pinfunction "A_1") (pintype "passive"))
      (node (ref "SW1") (pin "1") (pinfunction "1_1") (pintype "passive"))
    )
    (net (code "177") (name "Net-(H1-D+)") (class "Default")
      (node (ref "H1") (pin "3") (pinfunction "D+_3") (pintype "passive"))
      (node (ref "U11") (pin "5") (pinfunction "UD+_5") (pintype "bidirectional"))
    )
    (net (code "178") (name "Net-(H1-D-)") (class "Default")
      (node (ref "H1") (pin "2") (pinfunction "D-_2") (pintype "passive"))
      (node (ref "U11") (pin "6") (pinfunction "UD-_6") (pintype "bidirectional"))
    )
    (net (code "179") (name "Net-(OFF-A)") (class "Default")
      (node (ref "OFF") (pin "1") (pinfunction "A_1") (pintype "passive"))
      (node (ref "SW1") (pin "3") (pinfunction "3_3") (pintype "passive"))
    )
    (net (code "180") (name "Net-(R3-Pad2)") (class "Default")
      (node (ref "R3") (pin "2") (pinfunction "2_2") (pintype "passive"))
      (node (ref "SW1") (pin "2") (pinfunction "2_2") (pintype "passive"))
    )
    (net (code "181") (name "Net-(TTL-A)") (class "Default")
      (node (ref "SW1") (pin "4") (pinfunction "4_4") (pintype "passive"))
      (node (ref "TTL") (pin "1") (pinfunction "A_1") (pintype "passive"))
    )
    (net (code "182") (name "unconnected-(H1-Pad5)") (class "Default")
      (node (ref "H1") (pin "5") (pinfunction "5_5") (pintype "passive"))
    )
    (net (code "183") (name "unconnected-(H1-Pad6)") (class "Default")
      (node (ref "H1") (pin "6") (pinfunction "6_6") (pintype "passive"))
    )
    (net (code "184") (name "unconnected-(U11-NC.-Pad7)") (class "Default")
      (node (ref "U11") (pin "7") (pinfunction "NC._7") (pintype "passive+no_connect"))
    )
    (net (code "185") (name "unconnected-(U11-R232-Pad15)") (class "Default")
      (node (ref "U11") (pin "15") (pinfunction "R232_15") (pintype "input+no_connect"))
    )
    (net (code "186") (name "unconnected-(U11-~{CTS}-Pad9)") (class "Default")
      (node (ref "U11") (pin "9") (pinfunction "~{CTS}_9") (pintype "input+no_connect"))
    )
    (net (code "187") (name "unconnected-(U11-~{DCD}-Pad12)") (class "Default")
      (node (ref "U11") (pin "12") (pinfunction "~{DCD}_12") (pintype "input+no_connect"))
    )
    (net (code "188") (name "unconnected-(U11-~{DSR}-Pad10)") (class "Default")
      (node (ref "U11") (pin "10") (pinfunction "~{DSR}_10") (pintype "input+no_connect"))
    )
    (net (code "189") (name "unconnected-(U11-~{DTR}-Pad13)") (class "Default")
      (node (ref "U11") (pin "13") (pinfunction "~{DTR}_13") (pintype "output+no_connect"))
    )
    (net (code "190") (name "unconnected-(U11-~{OUT}-Pad8)") (class "Default")
      (node (ref "U11") (pin "8") (pinfunction "~{OUT}_8") (pintype "output+no_connect"))
    )
    (net (code "191") (name "unconnected-(U11-~{RI}-Pad11)") (class "Default")
      (node (ref "U11") (pin "11") (pinfunction "~{RI}_11") (pintype "input+no_connect"))
    )
    (net (code "192") (name "unconnected-(U11-~{RTS}-Pad14)") (class "Default")
      (node (ref "U11") (pin "14") (pinfunction "~{RTS}_14") (pintype "output+no_connect"))
    )
    (net (code "193") (name "unconnected-(U12-{slash}WP(IO2)-Pad3)") (class "Default")
      (node (ref "U12") (pin "3") (pinfunction "/WP(IO2)_3") (pintype "bidirectional"))
    )
  )
)
